# MMC_2_4_PSU.net
KiCad netlist of a schematic drawn in Altium Designer
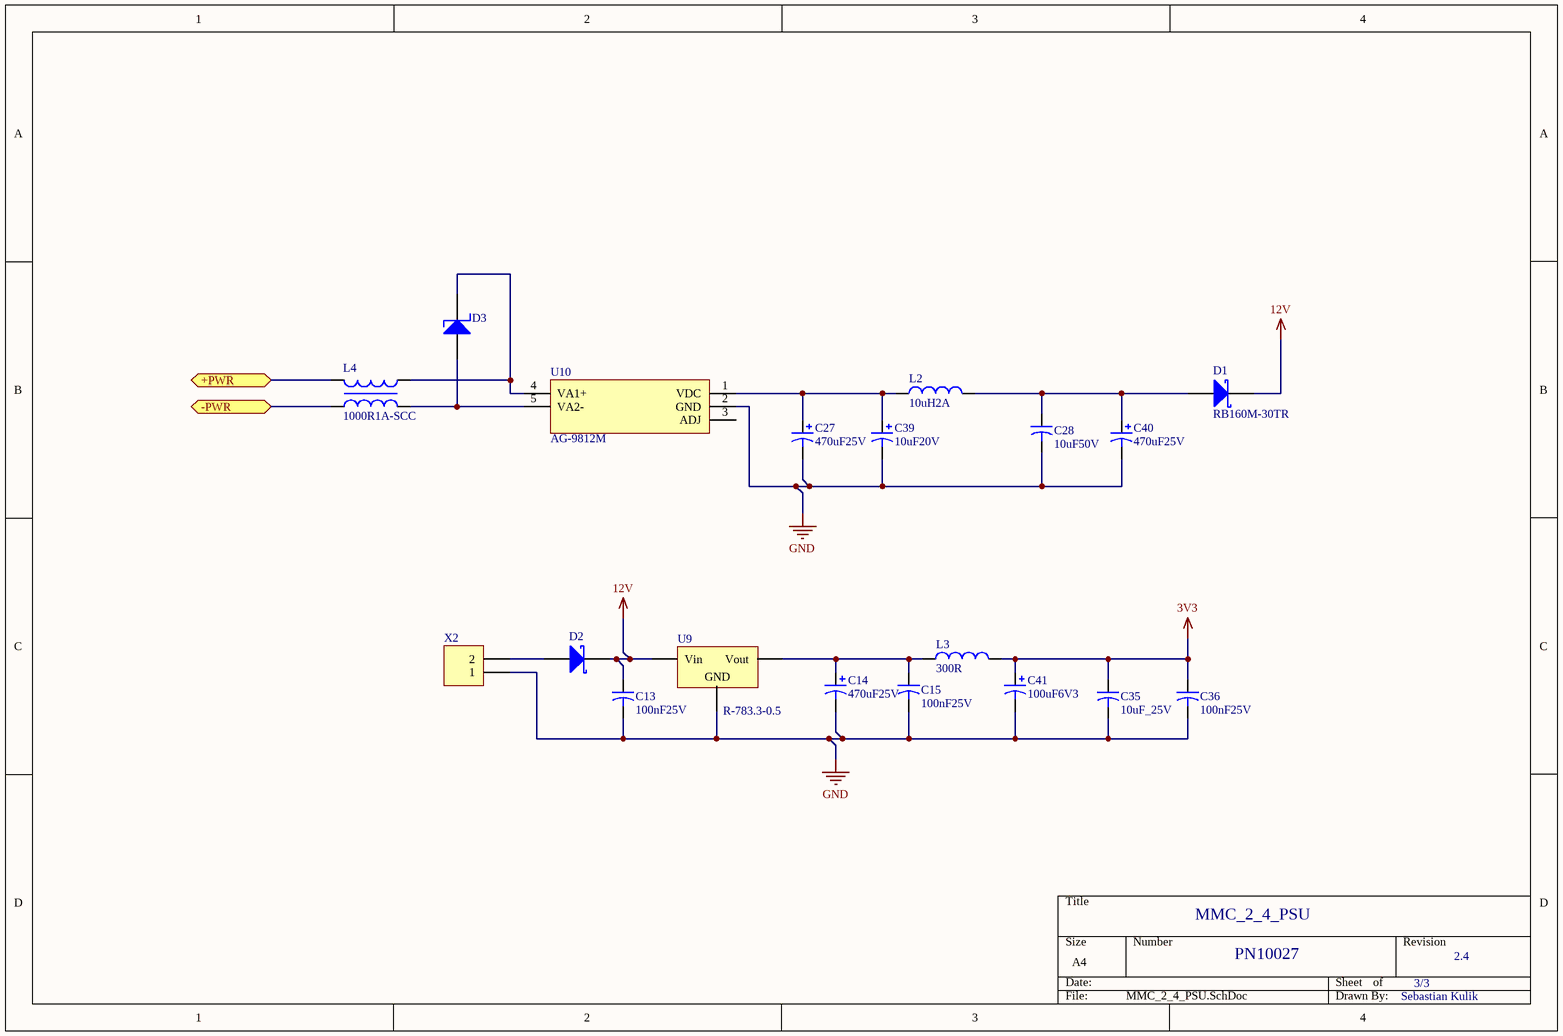
[diagram p0: MMC_2_4_PSU.SchDoc]

(export (version "E")
  (design (tool "Eeschema 10.0.6"))
  (components
    (comp (ref "C13")
      (value "100nF25V")
      (footprint "C0402")
      (description "AVX, X5R, 10%, 25V")
      (fields
        (field (name "MANUFACTURER") "AVX")
        (field (name "Comment") "100nF25V_0402")
        (field (name "PUBLISHER") "Sebastian Kulik")
      )
      (libsource (lib "Capacitors") (part "100nF25V_0402"))
    )
    (comp (ref "C14")
      (value "470uF25V")
      (footprint "Panasonic-FT-F_Case")
      (description "Panasonic, FT series")
      (fields
        (field (name "MANUFACTURER") "Panasonic")
        (field (name "Comment") "470uF25V_POL_FT")
        (field (name "PUBLISHER") "Sebastian Kulik")
      )
      (libsource (lib "Capacitors") (part "470uF25V_POL_FT"))
    )
    (comp (ref "C15")
      (value "100nF25V")
      (footprint "C0402")
      (description "AVX, X5R, 10%, 25V")
      (fields
        (field (name "MANUFACTURER") "AVX")
        (field (name "Comment") "100nF25V_0402")
        (field (name "PUBLISHER") "Sebastian Kulik")
      )
      (libsource (lib "Capacitors") (part "100nF25V_0402"))
    )
    (comp (ref "C27")
      (value "470uF25V")
      (footprint "Panasonic-FT-F_Case")
      (description "Panasonic, FT series")
      (fields
        (field (name "MANUFACTURER") "Panasonic")
        (field (name "Comment") "470uF25V_POL_FT")
        (field (name "PUBLISHER") "Sebastian Kulik")
      )
      (libsource (lib "Capacitors") (part "470uF25V_POL_FT"))
    )
    (comp (ref "C28")
      (value "10uF50V")
      (footprint "C1210")
      (description "AVX,  X7R, 10%, 50V")
      (fields
        (field (name "MANUFACTURER") "AVX")
        (field (name "Comment") "10uF50V_1210")
        (field (name "PUBLISHER") "Sebastian Kulik")
      )
      (libsource (lib "Capacitors") (part "10uF50V_1210"))
    )
    (comp (ref "C35")
      (value "10uF_25V")
      (footprint "C1210")
      (description "TDK  C series, X5R, 10%, 25V")
      (fields
        (field (name "MANUFACTURER") "TDK")
        (field (name "Comment") "10uF25V_1210")
        (field (name "PUBLISHER") "Sebastian Kulik")
      )
      (libsource (lib "Capacitors") (part "10uF25V_1210"))
    )
    (comp (ref "C36")
      (value "100nF25V")
      (footprint "C0402")
      (description "AVX, X5R, 10%, 25V")
      (fields
        (field (name "MANUFACTURER") "AVX")
        (field (name "Comment") "100nF25V_0402")
        (field (name "PUBLISHER") "Sebastian Kulik")
      )
      (libsource (lib "Capacitors") (part "100nF25V_0402"))
    )
    (comp (ref "C39")
      (value "10uF20V")
      (footprint "Vishay293D-B")
      (description "293 series, tantal, 10%, 10V")
      (fields
        (field (name "MANUFACTURER") "Vishay")
        (field (name "Comment") "10uF_20V_V293D-B")
        (field (name "PUBLISHER") "Sebastian Kulik")
      )
      (libsource (lib "Capacitors") (part "10uF_20V_V293D-B"))
    )
    (comp (ref "C40")
      (value "470uF25V")
      (footprint "Panasonic-FT-F_Case")
      (description "Panasonic, FT series")
      (fields
        (field (name "MANUFACTURER") "Panasonic")
        (field (name "Comment") "470uF25V_POL_FT")
        (field (name "PUBLISHER") "Sebastian Kulik")
      )
      (libsource (lib "Capacitors") (part "470uF25V_POL_FT"))
    )
    (comp (ref "C41")
      (value "100uF6V3")
      (footprint "Vishay293D-B")
      (description "293 series, tantal, 10%, 6.3V")
      (fields
        (field (name "MANUFACTURER") "Vishay")
        (field (name "Comment") "100uF_6V3_V293D-B")
        (field (name "PUBLISHER") "Sebastian Kulik")
      )
      (libsource (lib "Capacitors") (part "100uF_6V3_V293D-B"))
    )
    (comp (ref "D1")
      (value "RB160M-30TR")
      (footprint "SOD123")
      (description "Diode Schottky,2A,40V")
      (fields (field (name "MANUFACTURER") "Rohm") (field (name "PUBLISHER") "Sebastian Kulik"))
      (libsource (lib "Discrete") (part "RB160M-30TR"))
    )
    (comp (ref "D2")
      (value "RB160M-30TR")
      (footprint "SOD123")
      (description "Diode Schottky,2A,40V")
      (fields (field (name "MANUFACTURER") "Rohm") (field (name "PUBLISHER") "Sebastian Kulik"))
      (libsource (lib "Discrete") (part "RB160M-30TR"))
    )
    (comp (ref "D3")
      (value "SMAJ58A-E3/61")
      (footprint "DO214A")
      (description "TVS, 400W, 58V")
      (fields (field (name "MANUFACTURER") "Vishay") (field (name "PUBLISHER") "Sebastian Kulik"))
      (libsource (lib "Discrete") (part "SMAJ58A-E3/61"))
    )
    (comp (ref "L2")
      (value "10uH2A")
      (footprint "WE-PD2_1")
      (description "WE-PD2, 10uH2A")
      (fields (field (name "MANUFACTURER") "WE") (field (name "PUBLISHER") "Sebastian Kulik"))
      (libsource (lib "Passives") (part "10uH2A_WE-PD2"))
    )
    (comp (ref "L3")
      (value "300R")
      (footprint "L0603")
      (description "WE, Ferrit, 300Rx2A")
      (fields
        (field (name "MANUFACTURER") "WE")
        (field (name "Comment") "300R2A_0603")
        (field (name "PUBLISHER") "Sebastian Kulik")
      )
      (libsource (lib "Passives") (part "300R2A_0603"))
    )
    (comp (ref "L4")
      (value "1000R1A-SCC")
      (footprint "WE-SCC_7345")
      (description "Common mode choke")
      (fields (field (name "MANUFACTURER") "WE") (field (name "PUBLISHER") "Sebastian Kulik"))
      (libsource (lib "Passives") (part "1000R1A-SCC"))
    )
    (comp (ref "U9")
      (value "R-783.3-0.5")
      (footprint "R-783_3-0_5")
      (description "Voltage Regulator")
      (fields (field (name "MANUFACTURER") "Recom") (field (name "PUBLISHER") "Sebastian Kulik"))
      (libsource (lib "ICs") (part "Recom-R-783_3-0_5"))
    )
    (comp (ref "U10")
      (value "AG-9812M")
      (footprint "Ag9812M")
      (description "PoE, 12V")
      (fields (field (name "MANUFACTURER") "Silvertel") (field (name "PUBLISHER") "Sebastian Kulik"))
      (libsource (lib "ICs") (part "AG-9812M"))
    )
    (comp (ref "X2")
      (value "WR-TBL3127")
      (footprint "WR-TBL-3127")
      (description "Header 2 pin, horizontal,WR-TBL3127")
      (fields (field (name "MANUFACTURER") "WE") (field (name "PUBLISHER") "Sebastian Kulik"))
      (libsource (lib "Connectors") (part "Header-2-WR-TBL3127"))
    )
  )
  (nets
    (net (code "1") (name "/+PWR") (class "Default")
      (node (ref "L4") (pin "2") (pinfunction "2_2") (pintype "passive"))
    )
    (net (code "2") (name "/-PWR") (class "Default")
      (node (ref "L4") (pin "1") (pinfunction "1_1") (pintype "passive"))
    )
    (net (code "3") (name "3V3") (class "Default")
      (node (ref "C35") (pin "1") (pinfunction "1_1") (pintype "passive"))
      (node (ref "C36") (pin "1") (pinfunction "1_1") (pintype "passive"))
      (node (ref "C41") (pin "1") (pinfunction "1_1") (pintype "passive"))
      (node (ref "L3") (pin "2") (pinfunction "2_2") (pintype "passive"))
    )
    (net (code "4") (name "12V") (class "Default")
      (node (ref "C13") (pin "1") (pinfunction "1_1") (pintype "passive"))
      (node (ref "D1") (pin "1") (pinfunction "K_1") (pintype "passive"))
      (node (ref "D2") (pin "1") (pinfunction "K_1") (pintype "passive"))
      (node (ref "U9") (pin "1") (pinfunction "Vin_1") (pintype "passive"))
    )
    (net (code "5") (name "GND") (class "Default")
      (node (ref "C13") (pin "2") (pinfunction "2_2") (pintype "passive"))
      (node (ref "C14") (pin "2") (pinfunction "2_2") (pintype "passive"))
      (node (ref "C15") (pin "2") (pinfunction "2_2") (pintype "passive"))
      (node (ref "C27") (pin "2") (pinfunction "2_2") (pintype "passive"))
      (node (ref "C28") (pin "2") (pinfunction "2_2") (pintype "passive"))
      (node (ref "C35") (pin "2") (pinfunction "2_2") (pintype "passive"))
      (node (ref "C36") (pin "2") (pinfunction "2_2") (pintype "passive"))
      (node (ref "C39") (pin "2") (pinfunction "2_2") (pintype "passive"))
      (node (ref "C40") (pin "2") (pinfunction "2_2") (pintype "passive"))
      (node (ref "C41") (pin "2") (pinfunction "2_2") (pintype "passive"))
      (node (ref "U10") (pin "2") (pinfunction "GND_2") (pintype "passive"))
      (node (ref "U9") (pin "2") (pinfunction "GND_2") (pintype "passive"))
      (node (ref "X2") (pin "1") (pinfunction "1_1") (pintype "passive"))
    )
    (net (code "6") (name "Net-(D1-A)") (class "Default")
      (node (ref "C28") (pin "1") (pinfunction "1_1") (pintype "passive"))
      (node (ref "C40") (pin "1") (pinfunction "1_1") (pintype "passive"))
      (node (ref "D1") (pin "2") (pinfunction "A_2") (pintype "passive"))
      (node (ref "L2") (pin "2") (pinfunction "2_2") (pintype "passive"))
    )
    (net (code "7") (name "Net-(D2-A)") (class "Default")
      (node (ref "D2") (pin "2") (pinfunction "A_2") (pintype "passive"))
      (node (ref "X2") (pin "2") (pinfunction "2_2") (pintype "passive"))
    )
    (net (code "8") (name "Net-(D3-A)") (class "Default")
      (node (ref "D3") (pin "2") (pinfunction "A_2") (pintype "passive"))
      (node (ref "L4") (pin "3") (pinfunction "3_3") (pintype "passive"))
      (node (ref "U10") (pin "5") (pinfunction "VA2-_5") (pintype "passive"))
    )
    (net (code "9") (name "Net-(D3-K)") (class "Default")
      (node (ref "D3") (pin "1") (pinfunction "K_1") (pintype "passive"))
      (node (ref "L4") (pin "4") (pinfunction "4_4") (pintype "passive"))
      (node (ref "U10") (pin "4") (pinfunction "VA1+_4") (pintype "passive"))
    )
    (net (code "10") (name "Net-(U9-Vout)") (class "Default")
      (node (ref "C14") (pin "1") (pinfunction "1_1") (pintype "passive"))
      (node (ref "C15") (pin "1") (pinfunction "1_1") (pintype "passive"))
      (node (ref "L3") (pin "1") (pinfunction "1_1") (pintype "passive"))
      (node (ref "U9") (pin "3") (pinfunction "Vout_3") (pintype "passive"))
    )
    (net (code "11") (name "Net-(U10-VDC)") (class "Default")
      (node (ref "C27") (pin "1") (pinfunction "1_1") (pintype "passive"))
      (node (ref "C39") (pin "1") (pinfunction "1_1") (pintype "passive"))
      (node (ref "L2") (pin "1") (pinfunction "1_1") (pintype "passive"))
      (node (ref "U10") (pin "1") (pinfunction "VDC_1") (pintype "power_in"))
    )
    (net (code "12") (name "unconnected-(U10-ADJ-Pad3)") (class "Default")
      (node (ref "U10") (pin "3") (pinfunction "ADJ_3") (pintype "passive"))
    )
  )
)
